# MAPE-CUN-Large-018.net
KiCad netlist of a schematic drawn in EAGLE
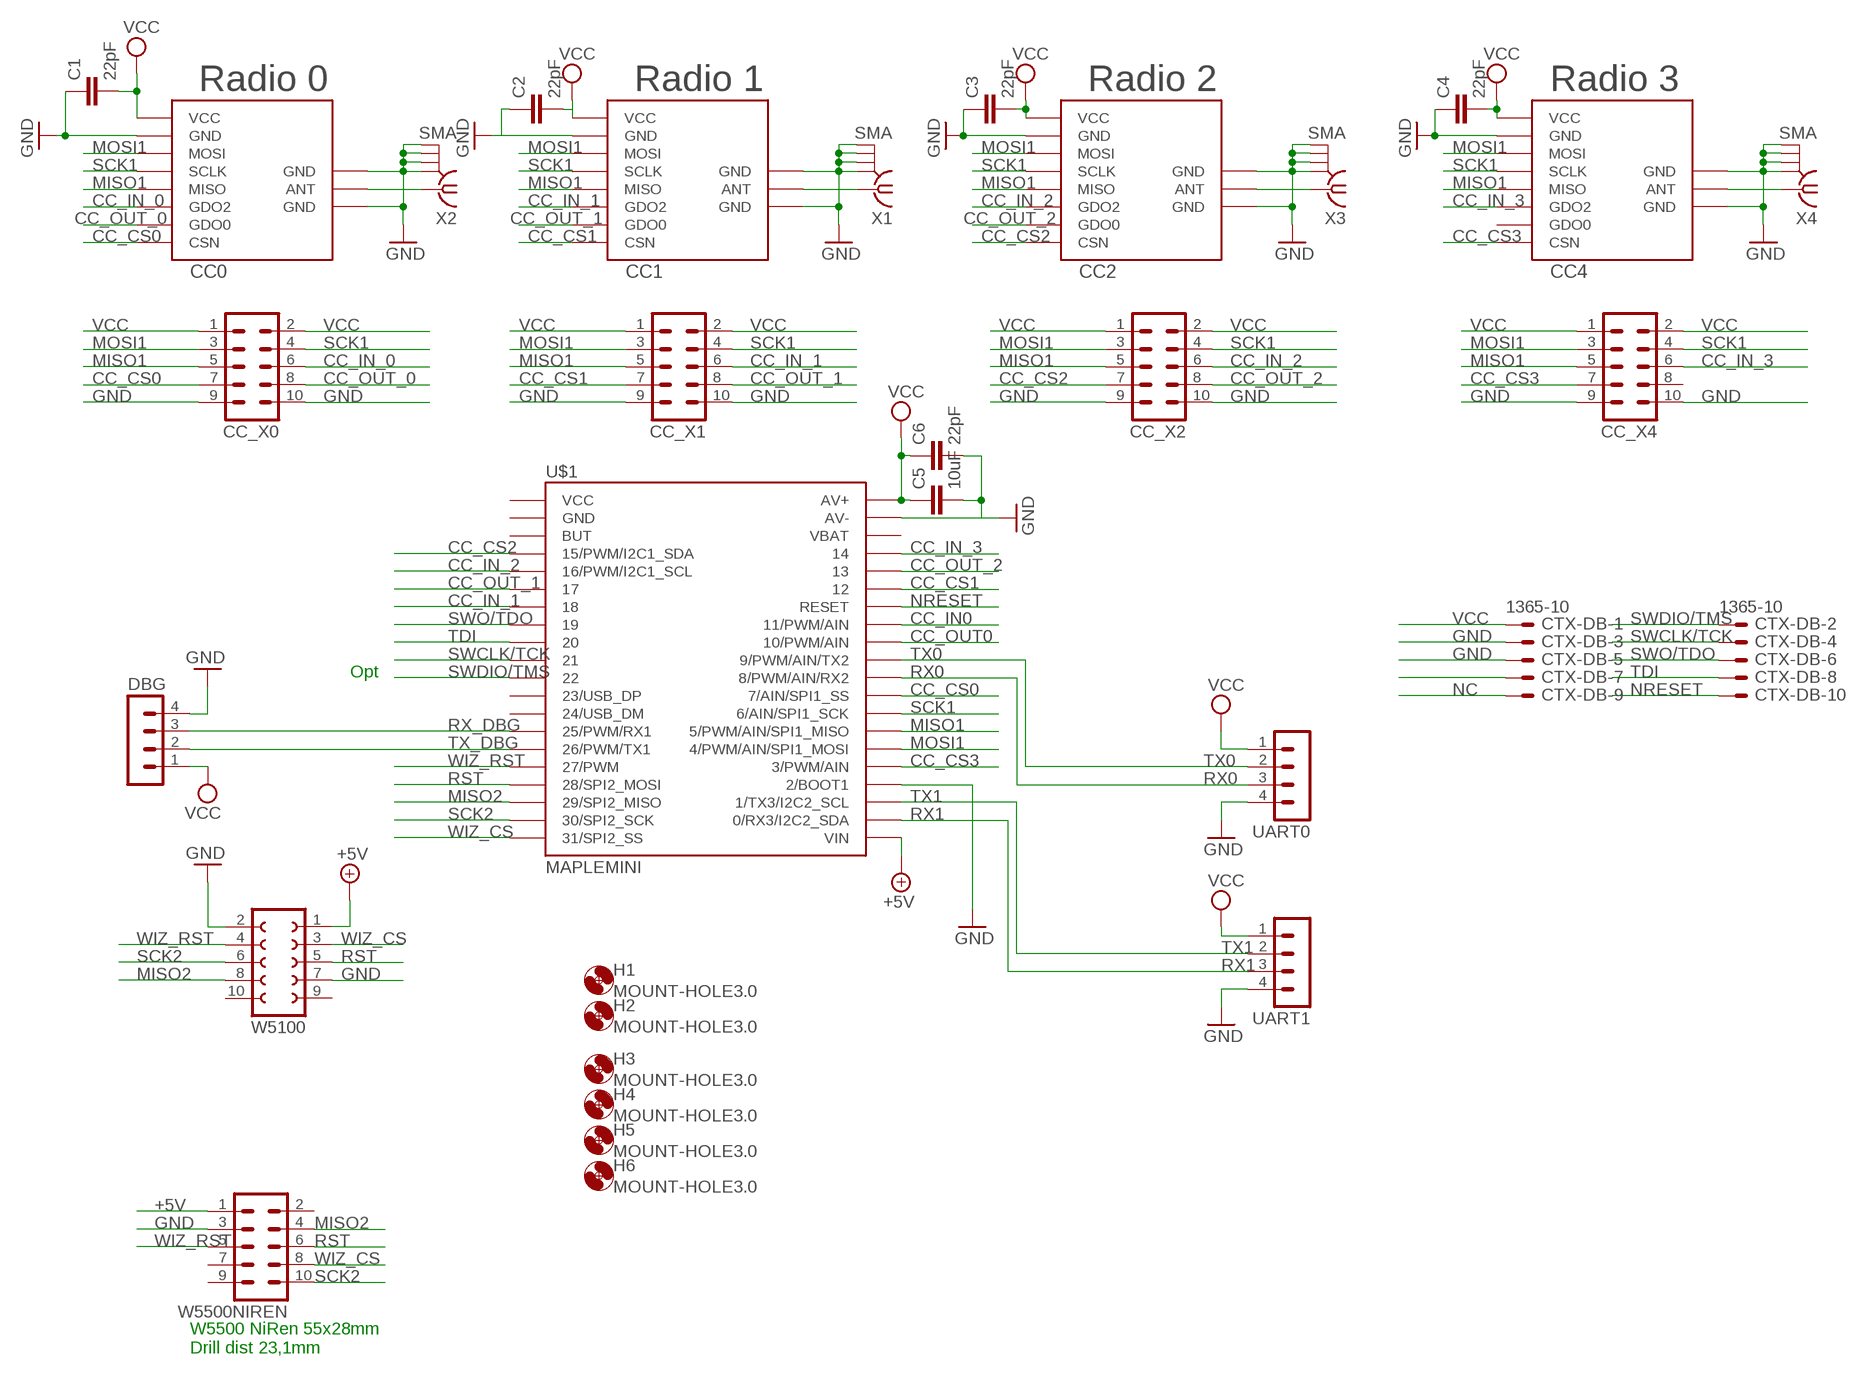
[diagram p0: schematic, sheet 1]

(export (version "E")
  (design (tool "Eeschema 10.0.6"))
  (components
    (comp (ref "C1")
      (value "22pF")
      (footprint "eagle-import:C0805")
      (libsource (lib "eagle-import") (part "C-EUC0805"))
    )
    (comp (ref "C2")
      (value "22pF")
      (footprint "eagle-import:C0805")
      (libsource (lib "eagle-import") (part "C-EUC0805"))
    )
    (comp (ref "C3")
      (value "22pF")
      (footprint "eagle-import:C0805")
      (libsource (lib "eagle-import") (part "C-EUC0805"))
    )
    (comp (ref "C4")
      (value "22pF")
      (footprint "eagle-import:C0805")
      (libsource (lib "eagle-import") (part "C-EUC0805"))
    )
    (comp (ref "C5")
      (value "10uF")
      (footprint "eagle-import:C1210")
      (libsource (lib "eagle-import") (part "C-EUC1210"))
    )
    (comp (ref "C6")
      (value "22pF")
      (footprint "eagle-import:C0805")
      (libsource (lib "eagle-import") (part "C-EUC0805"))
    )
    (comp (ref "CC0")
      (value "CC1101_MODULE1SMD")
      (footprint "eagle-import:CC1101_MODULE1_SMD")
      (libsource (lib "eagle-import") (part "CC1101_MODULE1SMD"))
    )
    (comp (ref "CC1")
      (value "CC1101_MODULE1SMD")
      (footprint "eagle-import:CC1101_MODULE1_SMD")
      (libsource (lib "eagle-import") (part "CC1101_MODULE1SMD"))
    )
    (comp (ref "CC2")
      (value "CC1101_MODULE1SMD")
      (footprint "eagle-import:CC1101_MODULE1_SMD")
      (libsource (lib "eagle-import") (part "CC1101_MODULE1SMD"))
    )
    (comp (ref "CC4")
      (value "CC1101_MODULE1SMD")
      (footprint "eagle-import:CC1101_MODULE1_SMD")
      (libsource (lib "eagle-import") (part "CC1101_MODULE1SMD"))
    )
    (comp (ref "CC_X0")
      (value "MA05-2")
      (footprint "eagle-import:MA05-2")
      (libsource (lib "eagle-import") (part "MA05-2"))
    )
    (comp (ref "CC_X1")
      (value "MA05-2")
      (footprint "eagle-import:MA05-2")
      (libsource (lib "eagle-import") (part "MA05-2"))
    )
    (comp (ref "CC_X2")
      (value "MA05-2")
      (footprint "eagle-import:MA05-2")
      (libsource (lib "eagle-import") (part "MA05-2"))
    )
    (comp (ref "CC_X4")
      (value "MA05-2")
      (footprint "eagle-import:MA05-2")
      (libsource (lib "eagle-import") (part "MA05-2"))
    )
    (comp (ref "CTX-DB")
      (value "1365-10")
      (footprint "eagle-import:1365-10")
      (libsource (lib "eagle-import") (part "1365-10"))
    )
    (comp (ref "DBG")
      (value "MA04-1")
      (footprint "eagle-import:MA04-1")
      (libsource (lib "eagle-import") (part "MA04-1"))
    )
    (comp (ref "H1")
      (value "MOUNT-HOLE3.0")
      (footprint "eagle-import:3,0")
      (libsource (lib "eagle-import") (part "MOUNT-HOLE3.0"))
    )
    (comp (ref "H2")
      (value "MOUNT-HOLE3.0")
      (footprint "eagle-import:3,0")
      (libsource (lib "eagle-import") (part "MOUNT-HOLE3.0"))
    )
    (comp (ref "H3")
      (value "MOUNT-HOLE3.0")
      (footprint "eagle-import:3,0")
      (libsource (lib "eagle-import") (part "MOUNT-HOLE3.0"))
    )
    (comp (ref "H4")
      (value "MOUNT-HOLE3.0")
      (footprint "eagle-import:3,0")
      (libsource (lib "eagle-import") (part "MOUNT-HOLE3.0"))
    )
    (comp (ref "H5")
      (value "MOUNT-HOLE3.0")
      (footprint "eagle-import:3,0")
      (libsource (lib "eagle-import") (part "MOUNT-HOLE3.0"))
    )
    (comp (ref "H6")
      (value "MOUNT-HOLE3.0")
      (footprint "eagle-import:3,0")
      (libsource (lib "eagle-import") (part "MOUNT-HOLE3.0"))
    )
    (comp (ref "U$1")
      (value "MAPLEMINI")
      (footprint "eagle-import:20-DIP")
      (libsource (lib "eagle-import") (part "MAPLEMINI"))
    )
    (comp (ref "UART0")
      (value "MA04-1")
      (footprint "eagle-import:MA04-1")
      (libsource (lib "eagle-import") (part "MA04-1"))
    )
    (comp (ref "UART1")
      (value "MA04-1")
      (footprint "eagle-import:MA04-1")
      (libsource (lib "eagle-import") (part "MA04-1"))
    )
    (comp (ref "W5100")
      (value "FE05-2")
      (footprint "eagle-import:FE05-2")
      (libsource (lib "eagle-import") (part "FE05-2"))
    )
    (comp (ref "W5500NIREN")
      (value "MA05-2")
      (footprint "eagle-import:MA05-2")
      (libsource (lib "eagle-import") (part "MA05-2"))
    )
    (comp (ref "X1")
      (value "SMA")
      (footprint "eagle-import:SMA")
      (libsource (lib "eagle-import") (part "SMA"))
    )
    (comp (ref "X2")
      (value "SMA")
      (footprint "eagle-import:SMA")
      (libsource (lib "eagle-import") (part "SMA"))
    )
    (comp (ref "X3")
      (value "SMA")
      (footprint "eagle-import:SMA")
      (libsource (lib "eagle-import") (part "SMA"))
    )
    (comp (ref "X4")
      (value "SMA")
      (footprint "eagle-import:SMA")
      (libsource (lib "eagle-import") (part "SMA"))
    )
  )
  (nets
    (net (code "1") (name "+5V") (class "Default")
      (node (ref "U$1") (pin "21") (pinfunction "VIN_21") (pintype "bidirectional"))
      (node (ref "W5100") (pin "1") (pinfunction "1_1") (pintype "passive"))
      (node (ref "W5500NIREN") (pin "1") (pinfunction "1_1") (pintype "passive"))
    )
    (net (code "2") (name "/CC_CS0") (class "Default")
      (node (ref "CC0") (pin "CSN") (pinfunction "CSN_CSN") (pintype "bidirectional"))
      (node (ref "CC_X0") (pin "7") (pinfunction "7_7") (pintype "passive"))
      (node (ref "U$1") (pin "29") (pinfunction "7/AIN/SPI1_SS_29") (pintype "bidirectional"))
    )
    (net (code "3") (name "/CC_CS1") (class "Default")
      (node (ref "CC1") (pin "CSN") (pinfunction "CSN_CSN") (pintype "bidirectional"))
      (node (ref "CC_X1") (pin "7") (pinfunction "7_7") (pintype "passive"))
      (node (ref "U$1") (pin "35") (pinfunction "12_35") (pintype "bidirectional"))
    )
    (net (code "4") (name "/CC_CS2") (class "Default")
      (node (ref "CC2") (pin "CSN") (pinfunction "CSN_CSN") (pintype "bidirectional"))
      (node (ref "CC_X2") (pin "7") (pinfunction "7_7") (pintype "passive"))
      (node (ref "U$1") (pin "4") (pinfunction "15/PWM/I2C1_SDA_4") (pintype "bidirectional"))
    )
    (net (code "5") (name "/CC_CS3") (class "Default")
      (node (ref "CC4") (pin "CSN") (pinfunction "CSN_CSN") (pintype "bidirectional"))
      (node (ref "CC_X4") (pin "7") (pinfunction "7_7") (pintype "passive"))
      (node (ref "U$1") (pin "25") (pinfunction "3/PWM/AIN_25") (pintype "bidirectional"))
    )
    (net (code "6") (name "/CC_IN0") (class "Default")
      (node (ref "U$1") (pin "33") (pinfunction "11/PWM/AIN_33") (pintype "bidirectional"))
    )
    (net (code "7") (name "/CC_IN_0") (class "Default")
      (node (ref "CC0") (pin "GDO2") (pinfunction "GDO2_GDO2") (pintype "bidirectional"))
      (node (ref "CC_X0") (pin "6") (pinfunction "6_6") (pintype "passive"))
    )
    (net (code "8") (name "/CC_IN_1") (class "Default")
      (node (ref "CC1") (pin "GDO2") (pinfunction "GDO2_GDO2") (pintype "bidirectional"))
      (node (ref "CC_X1") (pin "6") (pinfunction "6_6") (pintype "passive"))
      (node (ref "U$1") (pin "7") (pinfunction "18_7") (pintype "bidirectional"))
    )
    (net (code "9") (name "/CC_IN_2") (class "Default")
      (node (ref "CC2") (pin "GDO2") (pinfunction "GDO2_GDO2") (pintype "bidirectional"))
      (node (ref "CC_X2") (pin "6") (pinfunction "6_6") (pintype "passive"))
      (node (ref "U$1") (pin "5") (pinfunction "16/PWM/I2C1_SCL_5") (pintype "bidirectional"))
    )
    (net (code "10") (name "/CC_IN_3") (class "Default")
      (node (ref "CC4") (pin "GDO2") (pinfunction "GDO2_GDO2") (pintype "bidirectional"))
      (node (ref "CC_X4") (pin "6") (pinfunction "6_6") (pintype "passive"))
      (node (ref "U$1") (pin "37") (pinfunction "14_37") (pintype "bidirectional"))
    )
    (net (code "11") (name "/CC_OUT0") (class "Default")
      (node (ref "U$1") (pin "32") (pinfunction "10/PWM/AIN_32") (pintype "bidirectional"))
    )
    (net (code "12") (name "/CC_OUT_0") (class "Default")
      (node (ref "CC0") (pin "GDO0") (pinfunction "GDO0_GDO0") (pintype "bidirectional"))
      (node (ref "CC_X0") (pin "8") (pinfunction "8_8") (pintype "passive"))
    )
    (net (code "13") (name "/CC_OUT_1") (class "Default")
      (node (ref "CC1") (pin "GDO0") (pinfunction "GDO0_GDO0") (pintype "bidirectional"))
      (node (ref "CC_X1") (pin "8") (pinfunction "8_8") (pintype "passive"))
      (node (ref "U$1") (pin "6") (pinfunction "17_6") (pintype "bidirectional"))
    )
    (net (code "14") (name "/CC_OUT_2") (class "Default")
      (node (ref "CC2") (pin "GDO0") (pinfunction "GDO0_GDO0") (pintype "bidirectional"))
      (node (ref "CC_X2") (pin "8") (pinfunction "8_8") (pintype "passive"))
      (node (ref "U$1") (pin "36") (pinfunction "13_36") (pintype "bidirectional"))
    )
    (net (code "15") (name "/MISO1") (class "Default")
      (node (ref "CC0") (pin "MISO") (pinfunction "MISO_MISO") (pintype "bidirectional"))
      (node (ref "CC1") (pin "MISO") (pinfunction "MISO_MISO") (pintype "bidirectional"))
      (node (ref "CC2") (pin "MISO") (pinfunction "MISO_MISO") (pintype "bidirectional"))
      (node (ref "CC4") (pin "MISO") (pinfunction "MISO_MISO") (pintype "bidirectional"))
      (node (ref "CC_X0") (pin "5") (pinfunction "5_5") (pintype "passive"))
      (node (ref "CC_X1") (pin "5") (pinfunction "5_5") (pintype "passive"))
      (node (ref "CC_X2") (pin "5") (pinfunction "5_5") (pintype "passive"))
      (node (ref "CC_X4") (pin "5") (pinfunction "5_5") (pintype "passive"))
      (node (ref "U$1") (pin "27") (pinfunction "5/PWM/AIN/SPI1_MISO_27") (pintype "bidirectional"))
    )
    (net (code "16") (name "/MISO2") (class "Default")
      (node (ref "U$1") (pin "18") (pinfunction "29/SPI2_MISO_18") (pintype "bidirectional"))
      (node (ref "W5100") (pin "8") (pinfunction "8_8") (pintype "passive"))
      (node (ref "W5500NIREN") (pin "4") (pinfunction "4_4") (pintype "passive"))
    )
    (net (code "17") (name "/MOSI1") (class "Default")
      (node (ref "CC0") (pin "MOSI") (pinfunction "MOSI_MOSI") (pintype "bidirectional"))
      (node (ref "CC1") (pin "MOSI") (pinfunction "MOSI_MOSI") (pintype "bidirectional"))
      (node (ref "CC2") (pin "MOSI") (pinfunction "MOSI_MOSI") (pintype "bidirectional"))
      (node (ref "CC4") (pin "MOSI") (pinfunction "MOSI_MOSI") (pintype "bidirectional"))
      (node (ref "CC_X0") (pin "3") (pinfunction "3_3") (pintype "passive"))
      (node (ref "CC_X1") (pin "3") (pinfunction "3_3") (pintype "passive"))
      (node (ref "CC_X2") (pin "3") (pinfunction "3_3") (pintype "passive"))
      (node (ref "CC_X4") (pin "3") (pinfunction "3_3") (pintype "passive"))
      (node (ref "U$1") (pin "26") (pinfunction "4/PWM/AIN/SPI1_MOSI_26") (pintype "bidirectional"))
    )
    (net (code "18") (name "/NC") (class "Default")
      (node (ref "CTX-DB") (pin "9") (pinfunction "S_9") (pintype "passive"))
    )
    (net (code "19") (name "/NRESET") (class "Default")
      (node (ref "CTX-DB") (pin "10") (pinfunction "S_10") (pintype "passive"))
      (node (ref "U$1") (pin "34") (pinfunction "RESET_34") (pintype "bidirectional"))
    )
    (net (code "20") (name "/RST") (class "Default")
      (node (ref "U$1") (pin "17") (pinfunction "28/SPI2_MOSI_17") (pintype "bidirectional"))
      (node (ref "W5100") (pin "5") (pinfunction "5_5") (pintype "passive"))
      (node (ref "W5500NIREN") (pin "6") (pinfunction "6_6") (pintype "passive"))
    )
    (net (code "21") (name "/RX0") (class "Default")
      (node (ref "U$1") (pin "30") (pinfunction "8/PWM/AIN/RX2_30") (pintype "bidirectional"))
      (node (ref "UART0") (pin "3") (pinfunction "3_3") (pintype "passive"))
    )
    (net (code "22") (name "/RX1") (class "Default")
      (node (ref "U$1") (pin "22") (pinfunction "0/RX3/I2C2_SDA_22") (pintype "bidirectional"))
      (node (ref "UART1") (pin "3") (pinfunction "3_3") (pintype "passive"))
    )
    (net (code "23") (name "/RX_DBG") (class "Default")
      (node (ref "DBG") (pin "3") (pinfunction "3_3") (pintype "passive"))
      (node (ref "U$1") (pin "14") (pinfunction "25/PWM/RX1_14") (pintype "bidirectional"))
    )
    (net (code "24") (name "/SCK1") (class "Default")
      (node (ref "CC0") (pin "SCLK") (pinfunction "SCLK_SCLK") (pintype "bidirectional"))
      (node (ref "CC1") (pin "SCLK") (pinfunction "SCLK_SCLK") (pintype "bidirectional"))
      (node (ref "CC2") (pin "SCLK") (pinfunction "SCLK_SCLK") (pintype "bidirectional"))
      (node (ref "CC4") (pin "SCLK") (pinfunction "SCLK_SCLK") (pintype "bidirectional"))
      (node (ref "CC_X0") (pin "4") (pinfunction "4_4") (pintype "passive"))
      (node (ref "CC_X1") (pin "4") (pinfunction "4_4") (pintype "passive"))
      (node (ref "CC_X2") (pin "4") (pinfunction "4_4") (pintype "passive"))
      (node (ref "CC_X4") (pin "4") (pinfunction "4_4") (pintype "passive"))
      (node (ref "U$1") (pin "28") (pinfunction "6/AIN/SPI1_SCK_28") (pintype "bidirectional"))
    )
    (net (code "25") (name "/SCK2") (class "Default")
      (node (ref "U$1") (pin "19") (pinfunction "30/SPI2_SCK_19") (pintype "bidirectional"))
      (node (ref "W5100") (pin "6") (pinfunction "6_6") (pintype "passive"))
      (node (ref "W5500NIREN") (pin "10") (pinfunction "10_10") (pintype "passive"))
    )
    (net (code "26") (name "/SWCLK{slash}TCK") (class "Default")
      (node (ref "CTX-DB") (pin "4") (pinfunction "S_4") (pintype "passive"))
      (node (ref "U$1") (pin "10") (pinfunction "21_10") (pintype "bidirectional"))
    )
    (net (code "27") (name "/SWDIO{slash}TMS") (class "Default")
      (node (ref "CTX-DB") (pin "2") (pinfunction "S_2") (pintype "passive"))
      (node (ref "U$1") (pin "11") (pinfunction "22_11") (pintype "bidirectional"))
    )
    (net (code "28") (name "/SWO{slash}TDO") (class "Default")
      (node (ref "CTX-DB") (pin "6") (pinfunction "S_6") (pintype "passive"))
      (node (ref "U$1") (pin "8") (pinfunction "19_8") (pintype "bidirectional"))
    )
    (net (code "29") (name "/TDI") (class "Default")
      (node (ref "CTX-DB") (pin "8") (pinfunction "S_8") (pintype "passive"))
      (node (ref "U$1") (pin "9") (pinfunction "20_9") (pintype "bidirectional"))
    )
    (net (code "30") (name "/TX0") (class "Default")
      (node (ref "U$1") (pin "31") (pinfunction "9/PWM/AIN/TX2_31") (pintype "bidirectional"))
      (node (ref "UART0") (pin "2") (pinfunction "2_2") (pintype "passive"))
    )
    (net (code "31") (name "/TX1") (class "Default")
      (node (ref "U$1") (pin "23") (pinfunction "1/TX3/I2C2_SCL_23") (pintype "bidirectional"))
      (node (ref "UART1") (pin "2") (pinfunction "2_2") (pintype "passive"))
    )
    (net (code "32") (name "/TX_DBG") (class "Default")
      (node (ref "DBG") (pin "2") (pinfunction "2_2") (pintype "passive"))
      (node (ref "U$1") (pin "15") (pinfunction "26/PWM/TX1_15") (pintype "bidirectional"))
    )
    (net (code "33") (name "/WIZ_CS") (class "Default")
      (node (ref "U$1") (pin "20") (pinfunction "31/SPI2_SS_20") (pintype "bidirectional"))
      (node (ref "W5100") (pin "3") (pinfunction "3_3") (pintype "passive"))
      (node (ref "W5500NIREN") (pin "8") (pinfunction "8_8") (pintype "passive"))
    )
    (net (code "34") (name "/WIZ_RST") (class "Default")
      (node (ref "U$1") (pin "16") (pinfunction "27/PWM_16") (pintype "bidirectional"))
      (node (ref "W5100") (pin "4") (pinfunction "4_4") (pintype "passive"))
      (node (ref "W5500NIREN") (pin "5") (pinfunction "5_5") (pintype "passive"))
    )
    (net (code "35") (name "GND") (class "Default")
      (node (ref "C1") (pin "1") (pinfunction "1_1") (pintype "passive"))
      (node (ref "C2") (pin "1") (pinfunction "1_1") (pintype "passive"))
      (node (ref "C3") (pin "1") (pinfunction "1_1") (pintype "passive"))
      (node (ref "C4") (pin "1") (pinfunction "1_1") (pintype "passive"))
      (node (ref "C5") (pin "2") (pinfunction "2_2") (pintype "passive"))
      (node (ref "C6") (pin "2") (pinfunction "2_2") (pintype "passive"))
      (node (ref "CC0") (pin "GND@0") (pinfunction "GND_GND@0") (pintype "power_in"))
      (node (ref "CC0") (pin "GND@1") (pinfunction "GND_GND@1") (pintype "power_in"))
      (node (ref "CC0") (pin "GND@2") (pinfunction "GND_GND@2") (pintype "power_in"))
      (node (ref "CC1") (pin "GND@0") (pinfunction "GND_GND@0") (pintype "power_in"))
      (node (ref "CC1") (pin "GND@1") (pinfunction "GND_GND@1") (pintype "power_in"))
      (node (ref "CC1") (pin "GND@2") (pinfunction "GND_GND@2") (pintype "power_in"))
      (node (ref "CC2") (pin "GND@0") (pinfunction "GND_GND@0") (pintype "power_in"))
      (node (ref "CC2") (pin "GND@1") (pinfunction "GND_GND@1") (pintype "power_in"))
      (node (ref "CC2") (pin "GND@2") (pinfunction "GND_GND@2") (pintype "power_in"))
      (node (ref "CC4") (pin "GND@0") (pinfunction "GND_GND@0") (pintype "power_in"))
      (node (ref "CC4") (pin "GND@1") (pinfunction "GND_GND@1") (pintype "power_in"))
      (node (ref "CC4") (pin "GND@2") (pinfunction "GND_GND@2") (pintype "power_in"))
      (node (ref "CC_X0") (pin "10") (pinfunction "10_10") (pintype "passive"))
      (node (ref "CC_X0") (pin "9") (pinfunction "9_9") (pintype "passive"))
      (node (ref "CC_X1") (pin "10") (pinfunction "10_10") (pintype "passive"))
      (node (ref "CC_X1") (pin "9") (pinfunction "9_9") (pintype "passive"))
      (node (ref "CC_X2") (pin "10") (pinfunction "10_10") (pintype "passive"))
      (node (ref "CC_X2") (pin "9") (pinfunction "9_9") (pintype "passive"))
      (node (ref "CC_X4") (pin "10") (pinfunction "10_10") (pintype "passive"))
      (node (ref "CC_X4") (pin "9") (pinfunction "9_9") (pintype "passive"))
      (node (ref "CTX-DB") (pin "3") (pinfunction "S_3") (pintype "passive"))
      (node (ref "CTX-DB") (pin "5") (pinfunction "S_5") (pintype "passive"))
      (node (ref "DBG") (pin "4") (pinfunction "4_4") (pintype "passive"))
      (node (ref "U$1") (pin "24") (pinfunction "2/BOOT1_24") (pintype "bidirectional"))
      (node (ref "U$1") (pin "39") (pinfunction "AV-_39") (pintype "bidirectional"))
      (node (ref "UART0") (pin "4") (pinfunction "4_4") (pintype "passive"))
      (node (ref "UART1") (pin "4") (pinfunction "4_4") (pintype "passive"))
      (node (ref "W5100") (pin "2") (pinfunction "2_2") (pintype "passive"))
      (node (ref "W5100") (pin "7") (pinfunction "7_7") (pintype "passive"))
      (node (ref "W5500NIREN") (pin "3") (pinfunction "3_3") (pintype "passive"))
      (node (ref "X1") (pin "GND@1") (pinfunction "2_GND@1") (pintype "passive"))
      (node (ref "X1") (pin "GND@2") (pinfunction "3_GND@2") (pintype "passive"))
      (node (ref "X1") (pin "GND@3") (pinfunction "4_GND@3") (pintype "passive"))
      (node (ref "X1") (pin "GND@4") (pinfunction "5_GND@4") (pintype "passive"))
      (node (ref "X2") (pin "GND@1") (pinfunction "2_GND@1") (pintype "passive"))
      (node (ref "X2") (pin "GND@2") (pinfunction "3_GND@2") (pintype "passive"))
      (node (ref "X2") (pin "GND@3") (pinfunction "4_GND@3") (pintype "passive"))
      (node (ref "X2") (pin "GND@4") (pinfunction "5_GND@4") (pintype "passive"))
      (node (ref "X3") (pin "GND@1") (pinfunction "2_GND@1") (pintype "passive"))
      (node (ref "X3") (pin "GND@2") (pinfunction "3_GND@2") (pintype "passive"))
      (node (ref "X3") (pin "GND@3") (pinfunction "4_GND@3") (pintype "passive"))
      (node (ref "X3") (pin "GND@4") (pinfunction "5_GND@4") (pintype "passive"))
      (node (ref "X4") (pin "GND@1") (pinfunction "2_GND@1") (pintype "passive"))
      (node (ref "X4") (pin "GND@2") (pinfunction "3_GND@2") (pintype "passive"))
      (node (ref "X4") (pin "GND@3") (pinfunction "4_GND@3") (pintype "passive"))
      (node (ref "X4") (pin "GND@4") (pinfunction "5_GND@4") (pintype "passive"))
    )
    (net (code "36") (name "Net-(CC0-PadANT)") (class "Default")
      (node (ref "CC0") (pin "ANT") (pinfunction "ANT_ANT") (pintype "output"))
      (node (ref "X2") (pin "1") (pinfunction "1_1") (pintype "passive"))
    )
    (net (code "37") (name "Net-(CC1-PadANT)") (class "Default")
      (node (ref "CC1") (pin "ANT") (pinfunction "ANT_ANT") (pintype "output"))
      (node (ref "X1") (pin "1") (pinfunction "1_1") (pintype "passive"))
    )
    (net (code "38") (name "Net-(CC2-PadANT)") (class "Default")
      (node (ref "CC2") (pin "ANT") (pinfunction "ANT_ANT") (pintype "output"))
      (node (ref "X3") (pin "1") (pinfunction "1_1") (pintype "passive"))
    )
    (net (code "39") (name "Net-(CC4-PadANT)") (class "Default")
      (node (ref "CC4") (pin "ANT") (pinfunction "ANT_ANT") (pintype "output"))
      (node (ref "X4") (pin "1") (pinfunction "1_1") (pintype "passive"))
    )
    (net (code "40") (name "VCC") (class "Default")
      (node (ref "C1") (pin "2") (pinfunction "2_2") (pintype "passive"))
      (node (ref "C2") (pin "2") (pinfunction "2_2") (pintype "passive"))
      (node (ref "C3") (pin "2") (pinfunction "2_2") (pintype "passive"))
      (node (ref "C4") (pin "2") (pinfunction "2_2") (pintype "passive"))
      (node (ref "C5") (pin "1") (pinfunction "1_1") (pintype "passive"))
      (node (ref "C6") (pin "1") (pinfunction "1_1") (pintype "passive"))
      (node (ref "CC0") (pin "VCC") (pinfunction "VCC_VCC") (pintype "power_in"))
      (node (ref "CC1") (pin "VCC") (pinfunction "VCC_VCC") (pintype "power_in"))
      (node (ref "CC2") (pin "VCC") (pinfunction "VCC_VCC") (pintype "power_in"))
      (node (ref "CC4") (pin "VCC") (pinfunction "VCC_VCC") (pintype "power_in"))
      (node (ref "CC_X0") (pin "1") (pinfunction "1_1") (pintype "passive"))
      (node (ref "CC_X0") (pin "2") (pinfunction "2_2") (pintype "passive"))
      (node (ref "CC_X1") (pin "1") (pinfunction "1_1") (pintype "passive"))
      (node (ref "CC_X1") (pin "2") (pinfunction "2_2") (pintype "passive"))
      (node (ref "CC_X2") (pin "1") (pinfunction "1_1") (pintype "passive"))
      (node (ref "CC_X2") (pin "2") (pinfunction "2_2") (pintype "passive"))
      (node (ref "CC_X4") (pin "1") (pinfunction "1_1") (pintype "passive"))
      (node (ref "CC_X4") (pin "2") (pinfunction "2_2") (pintype "passive"))
      (node (ref "CTX-DB") (pin "1") (pinfunction "S_1") (pintype "passive"))
      (node (ref "DBG") (pin "1") (pinfunction "1_1") (pintype "passive"))
      (node (ref "U$1") (pin "40") (pinfunction "AV+_40") (pintype "bidirectional"))
      (node (ref "UART0") (pin "1") (pinfunction "1_1") (pintype "passive"))
      (node (ref "UART1") (pin "1") (pinfunction "1_1") (pintype "passive"))
    )
    (net (code "41") (name "unconnected-(CC4-PadGDO0)") (class "Default")
      (node (ref "CC4") (pin "GDO0") (pinfunction "GDO0_GDO0") (pintype "bidirectional"))
    )
    (net (code "42") (name "unconnected-(CC_X4-Pad8)") (class "Default")
      (node (ref "CC_X4") (pin "8") (pinfunction "8_8") (pintype "passive"))
    )
    (net (code "43") (name "unconnected-(CTX-DBH-S-Pad7)") (class "Default")
      (node (ref "CTX-DB") (pin "7") (pinfunction "S_7") (pintype "passive"))
    )
    (net (code "44") (name "unconnected-(U$1-23{slash}USB_DP-Pad12)") (class "Default")
      (node (ref "U$1") (pin "12") (pinfunction "23/USB_DP_12") (pintype "bidirectional"))
    )
    (net (code "45") (name "unconnected-(U$1-24{slash}USB_DM-Pad13)") (class "Default")
      (node (ref "U$1") (pin "13") (pinfunction "24/USB_DM_13") (pintype "bidirectional"))
    )
    (net (code "46") (name "unconnected-(U$1-BUT-Pad3)") (class "Default")
      (node (ref "U$1") (pin "3") (pinfunction "BUT_3") (pintype "bidirectional"))
    )
    (net (code "47") (name "unconnected-(U$1-GND-Pad2)") (class "Default")
      (node (ref "U$1") (pin "2") (pinfunction "GND_2") (pintype "bidirectional"))
    )
    (net (code "48") (name "unconnected-(U$1-VBAT-Pad38)") (class "Default")
      (node (ref "U$1") (pin "38") (pinfunction "VBAT_38") (pintype "bidirectional"))
    )
    (net (code "49") (name "unconnected-(U$1-VCC-Pad1)") (class "Default")
      (node (ref "U$1") (pin "1") (pinfunction "VCC_1") (pintype "bidirectional"))
    )
    (net (code "50") (name "unconnected-(W5100-Pad9)") (class "Default")
      (node (ref "W5100") (pin "9") (pinfunction "9_9") (pintype "passive"))
    )
    (net (code "51") (name "unconnected-(W5100-Pad10)") (class "Default")
      (node (ref "W5100") (pin "10") (pinfunction "10_10") (pintype "passive"))
    )
    (net (code "52") (name "unconnected-(W5500NIREN-Pad2)") (class "Default")
      (node (ref "W5500NIREN") (pin "2") (pinfunction "2_2") (pintype "passive"))
    )
    (net (code "53") (name "unconnected-(W5500NIREN-Pad7)") (class "Default")
      (node (ref "W5500NIREN") (pin "7") (pinfunction "7_7") (pintype "passive"))
    )
    (net (code "54") (name "unconnected-(W5500NIREN-Pad9)") (class "Default")
      (node (ref "W5500NIREN") (pin "9") (pinfunction "9_9") (pintype "passive"))
    )
  )
)
